# Si4455_Breakout.net
KiCad netlist of a schematic drawn in EAGLE
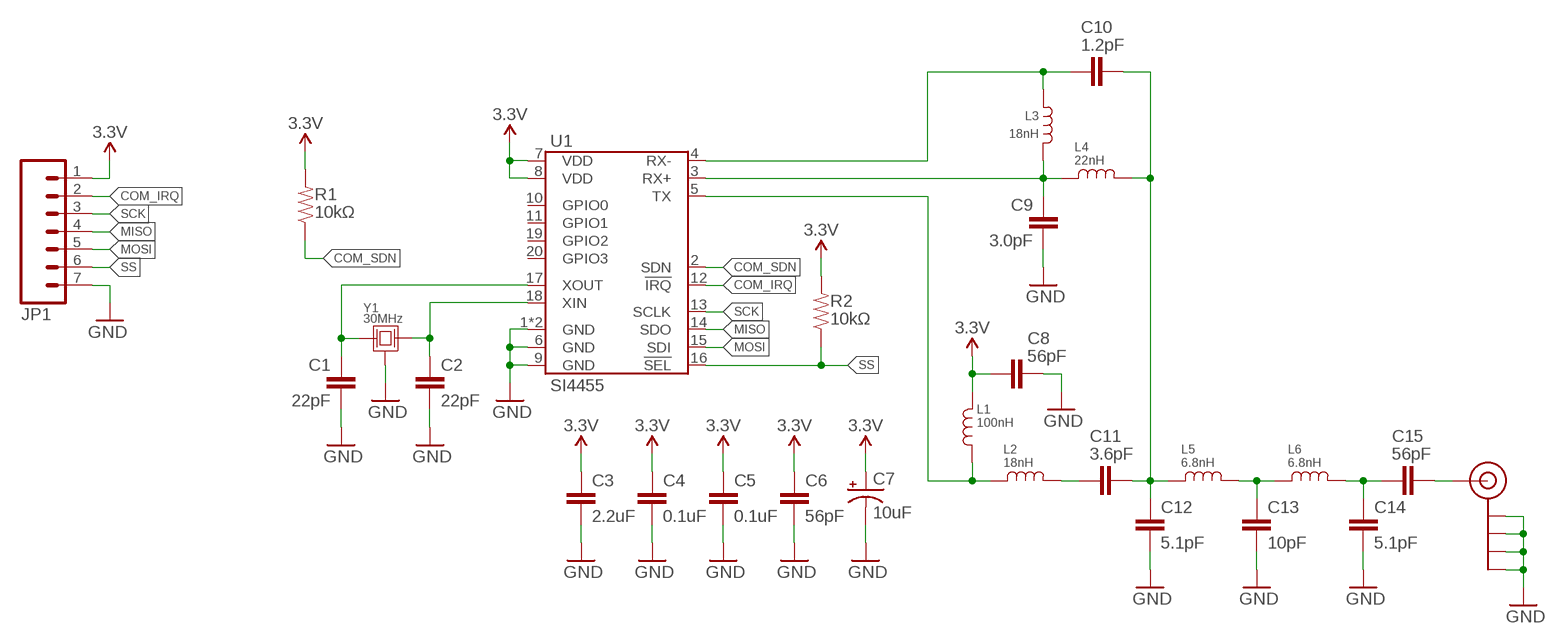
[diagram p0: schematic, sheet 1]

(export (version "E")
  (design (tool "Eeschema 10.0.6"))
  (components
    (comp (ref "C1")
      (value "22pF")
      (footprint "eagle-import:0402-CAP")
      (libsource (lib "eagle-import") (part "CAP-0402"))
    )
    (comp (ref "C2")
      (value "22pF")
      (footprint "eagle-import:0402-CAP")
      (libsource (lib "eagle-import") (part "CAP-0402"))
    )
    (comp (ref "C3")
      (value "2.2uF")
      (footprint "eagle-import:0402-CAP")
      (libsource (lib "eagle-import") (part "CAP-0402"))
    )
    (comp (ref "C4")
      (value "0.1uF")
      (footprint "eagle-import:0402-CAP")
      (libsource (lib "eagle-import") (part "CAP-0402"))
    )
    (comp (ref "C5")
      (value "0.1uF")
      (footprint "eagle-import:0402-CAP")
      (libsource (lib "eagle-import") (part "CAP-0402"))
    )
    (comp (ref "C6")
      (value "56pF")
      (footprint "eagle-import:0402-CAP")
      (libsource (lib "eagle-import") (part "CAP-0402"))
    )
    (comp (ref "C7")
      (value "10uF")
      (footprint "eagle-import:0805-CAP_POL")
      (libsource (lib "eagle-import") (part "CAP_POL0805"))
    )
    (comp (ref "C8")
      (value "56pF")
      (footprint "eagle-import:0402-CAP")
      (libsource (lib "eagle-import") (part "CAP-0402"))
    )
    (comp (ref "C9")
      (value "3.0pF")
      (footprint "eagle-import:0402-CAP")
      (libsource (lib "eagle-import") (part "CAP-0402"))
    )
    (comp (ref "C10")
      (value "1.2pF")
      (footprint "eagle-import:0402-CAP")
      (libsource (lib "eagle-import") (part "CAP-0402"))
    )
    (comp (ref "C11")
      (value "3.6pF")
      (footprint "eagle-import:0402-CAP")
      (libsource (lib "eagle-import") (part "CAP-0402"))
    )
    (comp (ref "C12")
      (value "5.1pF")
      (footprint "eagle-import:0402-CAP")
      (libsource (lib "eagle-import") (part "CAP-0402"))
    )
    (comp (ref "C13")
      (value "10pF")
      (footprint "eagle-import:0402-CAP")
      (libsource (lib "eagle-import") (part "CAP-0402"))
    )
    (comp (ref "C14")
      (value "5.1pF")
      (footprint "eagle-import:0402-CAP")
      (libsource (lib "eagle-import") (part "CAP-0402"))
    )
    (comp (ref "C15")
      (value "56pF")
      (footprint "eagle-import:0402-CAP")
      (libsource (lib "eagle-import") (part "CAP-0402"))
    )
    (comp (ref "J$1")
      (value "SMA_EDGE")
      (footprint "eagle-import:SMA-EDGE")
      (libsource (lib "eagle-import") (part "SMA_EDGE"))
    )
    (comp (ref "JP1")
      (value "M07")
      (footprint "eagle-import:1X07")
      (libsource (lib "eagle-import") (part "M07"))
    )
    (comp (ref "L1")
      (value "100nH")
      (footprint "eagle-import:0402-INDUCTOR")
      (libsource (lib "eagle-import") (part "INDUCTOR-0402"))
    )
    (comp (ref "L2")
      (value "18nH")
      (footprint "eagle-import:0402-INDUCTOR")
      (libsource (lib "eagle-import") (part "INDUCTOR-0402"))
    )
    (comp (ref "L3")
      (value "18nH")
      (footprint "eagle-import:0402-INDUCTOR")
      (libsource (lib "eagle-import") (part "INDUCTOR-0402"))
    )
    (comp (ref "L4")
      (value "22nH")
      (footprint "eagle-import:0402-INDUCTOR")
      (libsource (lib "eagle-import") (part "INDUCTOR-0402"))
    )
    (comp (ref "L5")
      (value "6.8nH")
      (footprint "eagle-import:0402-INDUCTOR")
      (libsource (lib "eagle-import") (part "INDUCTOR-0402"))
    )
    (comp (ref "L6")
      (value "6.8nH")
      (footprint "eagle-import:0402-INDUCTOR")
      (libsource (lib "eagle-import") (part "INDUCTOR-0402"))
    )
    (comp (ref "R1")
      (value "10kΩ")
      (footprint "eagle-import:0402-RES")
      (libsource (lib "eagle-import") (part "RESISTOR"))
    )
    (comp (ref "R2")
      (value "10kΩ")
      (footprint "eagle-import:0402-RES")
      (libsource (lib "eagle-import") (part "RESISTOR"))
    )
    (comp (ref "U1")
      (value "SI4455")
      (footprint "eagle-import:SI4455")
      (libsource (lib "eagle-import") (part "SI4455"))
    )
    (comp (ref "Y1")
      (value "30MHz")
      (footprint "eagle-import:FA-238")
      (libsource (lib "eagle-import") (part "CRYSTAL-3.2X2.5"))
    )
  )
  (nets
    (net (code "1") (name "3.3V") (class "Default")
      (node (ref "C3") (pin "1") (pinfunction "1_1") (pintype "passive"))
      (node (ref "C4") (pin "1") (pinfunction "1_1") (pintype "passive"))
      (node (ref "C5") (pin "1") (pinfunction "1_1") (pintype "passive"))
      (node (ref "C6") (pin "1") (pinfunction "1_1") (pintype "passive"))
      (node (ref "C7") (pin "A") (pinfunction "+_A") (pintype "passive"))
      (node (ref "C8") (pin "1") (pinfunction "1_1") (pintype "passive"))
      (node (ref "JP1") (pin "1") (pinfunction "1_1") (pintype "passive"))
      (node (ref "L1") (pin "2") (pinfunction "P$2_2") (pintype "bidirectional"))
      (node (ref "R1") (pin "2") (pinfunction "2_2") (pintype "passive"))
      (node (ref "R2") (pin "2") (pinfunction "2_2") (pintype "passive"))
      (node (ref "U1") (pin "7") (pinfunction "VDD_7") (pintype "bidirectional"))
      (node (ref "U1") (pin "8") (pinfunction "VDD_8") (pintype "bidirectional"))
    )
    (net (code "2") (name "COM_IRQ") (class "Default")
      (node (ref "JP1") (pin "2") (pinfunction "2_2") (pintype "passive"))
      (node (ref "U1") (pin "12") (pinfunction "~{IRQ}_12") (pintype "bidirectional"))
    )
    (net (code "3") (name "COM_SDN") (class "Default")
      (node (ref "R1") (pin "1") (pinfunction "1_1") (pintype "passive"))
      (node (ref "U1") (pin "2") (pinfunction "SDN_2") (pintype "bidirectional"))
    )
    (net (code "4") (name "GND") (class "Default")
      (node (ref "C1") (pin "2") (pinfunction "2_2") (pintype "passive"))
      (node (ref "C12") (pin "2") (pinfunction "2_2") (pintype "passive"))
      (node (ref "C13") (pin "2") (pinfunction "2_2") (pintype "passive"))
      (node (ref "C14") (pin "2") (pinfunction "2_2") (pintype "passive"))
      (node (ref "C2") (pin "2") (pinfunction "2_2") (pintype "passive"))
      (node (ref "C3") (pin "2") (pinfunction "2_2") (pintype "passive"))
      (node (ref "C4") (pin "2") (pinfunction "2_2") (pintype "passive"))
      (node (ref "C5") (pin "2") (pinfunction "2_2") (pintype "passive"))
      (node (ref "C6") (pin "2") (pinfunction "2_2") (pintype "passive"))
      (node (ref "C7") (pin "C") (pinfunction "-_C") (pintype "passive"))
      (node (ref "C8") (pin "2") (pinfunction "2_2") (pintype "passive"))
      (node (ref "C9") (pin "2") (pinfunction "2_2") (pintype "passive"))
      (node (ref "J$1") (pin "GND@0") (pinfunction "GND_GND@0") (pintype "bidirectional"))
      (node (ref "J$1") (pin "GND@1") (pinfunction "GND_GND@1") (pintype "bidirectional"))
      (node (ref "J$1") (pin "GND@2") (pinfunction "GND_GND@2") (pintype "bidirectional"))
      (node (ref "J$1") (pin "GND@3") (pinfunction "GND_GND@3") (pintype "bidirectional"))
      (node (ref "JP1") (pin "7") (pinfunction "7_7") (pintype "passive"))
      (node (ref "U1") (pin "1") (pinfunction "GND_1") (pintype "bidirectional"))
      (node (ref "U1") (pin "6") (pinfunction "GND_6") (pintype "bidirectional"))
      (node (ref "U1") (pin "9") (pinfunction "GND_9") (pintype "bidirectional"))
      (node (ref "U1") (pin "EP") (pinfunction "GND_EP") (pintype "bidirectional"))
      (node (ref "Y1") (pin "2") (pinfunction "GND_2") (pintype "bidirectional"))
      (node (ref "Y1") (pin "4") (pinfunction "GND_4") (pintype "bidirectional"))
    )
    (net (code "5") (name "MISO") (class "Default")
      (node (ref "JP1") (pin "4") (pinfunction "4_4") (pintype "passive"))
      (node (ref "U1") (pin "14") (pinfunction "SDO_14") (pintype "bidirectional"))
    )
    (net (code "6") (name "MOSI") (class "Default")
      (node (ref "JP1") (pin "5") (pinfunction "5_5") (pintype "passive"))
      (node (ref "U1") (pin "15") (pinfunction "SDI_15") (pintype "bidirectional"))
    )
    (net (code "7") (name "Net-(J$1-SIGNAL)") (class "Default")
      (node (ref "C15") (pin "2") (pinfunction "2_2") (pintype "passive"))
      (node (ref "J$1") (pin "SIG") (pinfunction "SIGNAL_SIG") (pintype "bidirectional"))
    )
    (net (code "8") (name "Net-(L1-P$1)") (class "Default")
      (node (ref "L1") (pin "1") (pinfunction "P$1_1") (pintype "bidirectional"))
      (node (ref "L2") (pin "1") (pinfunction "P$1_1") (pintype "bidirectional"))
      (node (ref "U1") (pin "5") (pinfunction "TX_5") (pintype "bidirectional"))
    )
    (net (code "9") (name "Net-(L2-P$2)") (class "Default")
      (node (ref "C11") (pin "1") (pinfunction "1_1") (pintype "passive"))
      (node (ref "L2") (pin "2") (pinfunction "P$2_2") (pintype "bidirectional"))
    )
    (net (code "10") (name "Net-(L3-P$1)") (class "Default")
      (node (ref "C9") (pin "1") (pinfunction "1_1") (pintype "passive"))
      (node (ref "L3") (pin "1") (pinfunction "P$1_1") (pintype "bidirectional"))
      (node (ref "L4") (pin "1") (pinfunction "P$1_1") (pintype "bidirectional"))
      (node (ref "U1") (pin "3") (pinfunction "RX+_3") (pintype "bidirectional"))
    )
    (net (code "11") (name "Net-(L3-P$2)") (class "Default")
      (node (ref "C10") (pin "1") (pinfunction "1_1") (pintype "passive"))
      (node (ref "L3") (pin "2") (pinfunction "P$2_2") (pintype "bidirectional"))
      (node (ref "U1") (pin "4") (pinfunction "RX-_4") (pintype "bidirectional"))
    )
    (net (code "12") (name "Net-(L4-P$2)") (class "Default")
      (node (ref "C10") (pin "2") (pinfunction "2_2") (pintype "passive"))
      (node (ref "C11") (pin "2") (pinfunction "2_2") (pintype "passive"))
      (node (ref "C12") (pin "1") (pinfunction "1_1") (pintype "passive"))
      (node (ref "L4") (pin "2") (pinfunction "P$2_2") (pintype "bidirectional"))
      (node (ref "L5") (pin "1") (pinfunction "P$1_1") (pintype "bidirectional"))
    )
    (net (code "13") (name "Net-(L5-P$2)") (class "Default")
      (node (ref "C13") (pin "1") (pinfunction "1_1") (pintype "passive"))
      (node (ref "L5") (pin "2") (pinfunction "P$2_2") (pintype "bidirectional"))
      (node (ref "L6") (pin "1") (pinfunction "P$1_1") (pintype "bidirectional"))
    )
    (net (code "14") (name "Net-(L6-P$2)") (class "Default")
      (node (ref "C14") (pin "1") (pinfunction "1_1") (pintype "passive"))
      (node (ref "C15") (pin "1") (pinfunction "1_1") (pintype "passive"))
      (node (ref "L6") (pin "2") (pinfunction "P$2_2") (pintype "bidirectional"))
    )
    (net (code "15") (name "Net-(U1-XIN)") (class "Default")
      (node (ref "C2") (pin "1") (pinfunction "1_1") (pintype "passive"))
      (node (ref "U1") (pin "18") (pinfunction "XIN_18") (pintype "bidirectional"))
      (node (ref "Y1") (pin "3") (pinfunction "2_3") (pintype "bidirectional"))
    )
    (net (code "16") (name "Net-(U1-XOUT)") (class "Default")
      (node (ref "C1") (pin "1") (pinfunction "1_1") (pintype "passive"))
      (node (ref "U1") (pin "17") (pinfunction "XOUT_17") (pintype "bidirectional"))
      (node (ref "Y1") (pin "1") (pinfunction "1_1") (pintype "bidirectional"))
    )
    (net (code "17") (name "SCK") (class "Default")
      (node (ref "JP1") (pin "3") (pinfunction "3_3") (pintype "passive"))
      (node (ref "U1") (pin "13") (pinfunction "SCLK_13") (pintype "bidirectional"))
    )
    (net (code "18") (name "SS") (class "Default")
      (node (ref "JP1") (pin "6") (pinfunction "6_6") (pintype "passive"))
      (node (ref "R2") (pin "1") (pinfunction "1_1") (pintype "passive"))
      (node (ref "U1") (pin "16") (pinfunction "~{SEL}_16") (pintype "bidirectional"))
    )
    (net (code "19") (name "unconnected-(U1-GPIO0-Pad10)") (class "Default")
      (node (ref "U1") (pin "10") (pinfunction "GPIO0_10") (pintype "bidirectional"))
    )
    (net (code "20") (name "unconnected-(U1-GPIO1-Pad11)") (class "Default")
      (node (ref "U1") (pin "11") (pinfunction "GPIO1_11") (pintype "bidirectional"))
    )
    (net (code "21") (name "unconnected-(U1-GPIO2-Pad19)") (class "Default")
      (node (ref "U1") (pin "19") (pinfunction "GPIO2_19") (pintype "bidirectional"))
    )
    (net (code "22") (name "unconnected-(U1-GPIO3-Pad20)") (class "Default")
      (node (ref "U1") (pin "20") (pinfunction "GPIO3_20") (pintype "bidirectional"))
    )
  )
)
